# currentRead.net
KiCad netlist of a schematic drawn in Altium Designer
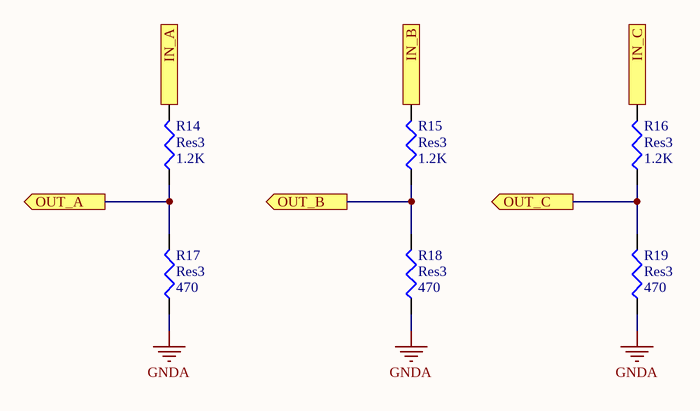
[diagram p0: currentRead.SchDoc]

(export (version "E")
  (design (tool "Eeschema 10.0.6"))
  (components
    (comp (ref "R14")
      (value "Res3")
      (footprint "12Z-2010")
      (description "Resistor")
      (fields (field (name "ALTIUM_VALUE") "1.2K") (field (name "PUBLISHER") "Altium Limited"))
      (libsource (lib "Miscellaneous Devices") (part "Res3"))
    )
    (comp (ref "R15")
      (value "Res3")
      (footprint "12Z-2010")
      (description "Resistor")
      (fields (field (name "ALTIUM_VALUE") "1.2K") (field (name "PUBLISHER") "Altium Limited"))
      (libsource (lib "Miscellaneous Devices") (part "Res3"))
    )
    (comp (ref "R16")
      (value "Res3")
      (footprint "12Z-2010")
      (description "Resistor")
      (fields (field (name "ALTIUM_VALUE") "1.2K") (field (name "PUBLISHER") "Altium Limited"))
      (libsource (lib "Miscellaneous Devices") (part "Res3"))
    )
    (comp (ref "R17")
      (value "Res3")
      (footprint "12Z-2010")
      (description "Resistor")
      (fields (field (name "ALTIUM_VALUE") "470") (field (name "PUBLISHER") "Altium Limited"))
      (libsource (lib "Miscellaneous Devices") (part "Res3"))
    )
    (comp (ref "R18")
      (value "Res3")
      (footprint "12Z-2010")
      (description "Resistor")
      (fields (field (name "ALTIUM_VALUE") "470") (field (name "PUBLISHER") "Altium Limited"))
      (libsource (lib "Miscellaneous Devices") (part "Res3"))
    )
    (comp (ref "R19")
      (value "Res3")
      (footprint "12Z-2010")
      (description "Resistor")
      (fields (field (name "ALTIUM_VALUE") "470") (field (name "PUBLISHER") "Altium Limited"))
      (libsource (lib "Miscellaneous Devices") (part "Res3"))
    )
  )
  (nets
    (net (code "1") (name "/IN_A") (class "Default")
      (node (ref "R14") (pin "2") (pinfunction "2_2") (pintype "passive"))
    )
    (net (code "2") (name "/IN_B") (class "Default")
      (node (ref "R15") (pin "2") (pinfunction "2_2") (pintype "passive"))
    )
    (net (code "3") (name "/IN_C") (class "Default")
      (node (ref "R16") (pin "2") (pinfunction "2_2") (pintype "passive"))
    )
    (net (code "4") (name "/OUT_A") (class "Default")
      (node (ref "R14") (pin "1") (pinfunction "1_1") (pintype "passive"))
      (node (ref "R17") (pin "2") (pinfunction "2_2") (pintype "passive"))
    )
    (net (code "5") (name "/OUT_B") (class "Default")
      (node (ref "R15") (pin "1") (pinfunction "1_1") (pintype "passive"))
      (node (ref "R18") (pin "2") (pinfunction "2_2") (pintype "passive"))
    )
    (net (code "6") (name "/OUT_C") (class "Default")
      (node (ref "R16") (pin "1") (pinfunction "1_1") (pintype "passive"))
      (node (ref "R19") (pin "2") (pinfunction "2_2") (pintype "passive"))
    )
    (net (code "7") (name "GNDA") (class "Default")
      (node (ref "R17") (pin "1") (pinfunction "1_1") (pintype "passive"))
      (node (ref "R18") (pin "1") (pinfunction "1_1") (pintype "passive"))
      (node (ref "R19") (pin "1") (pinfunction "1_1") (pintype "passive"))
    )
  )
)
